# ETH.net
KiCad netlist of a schematic drawn in Altium Designer
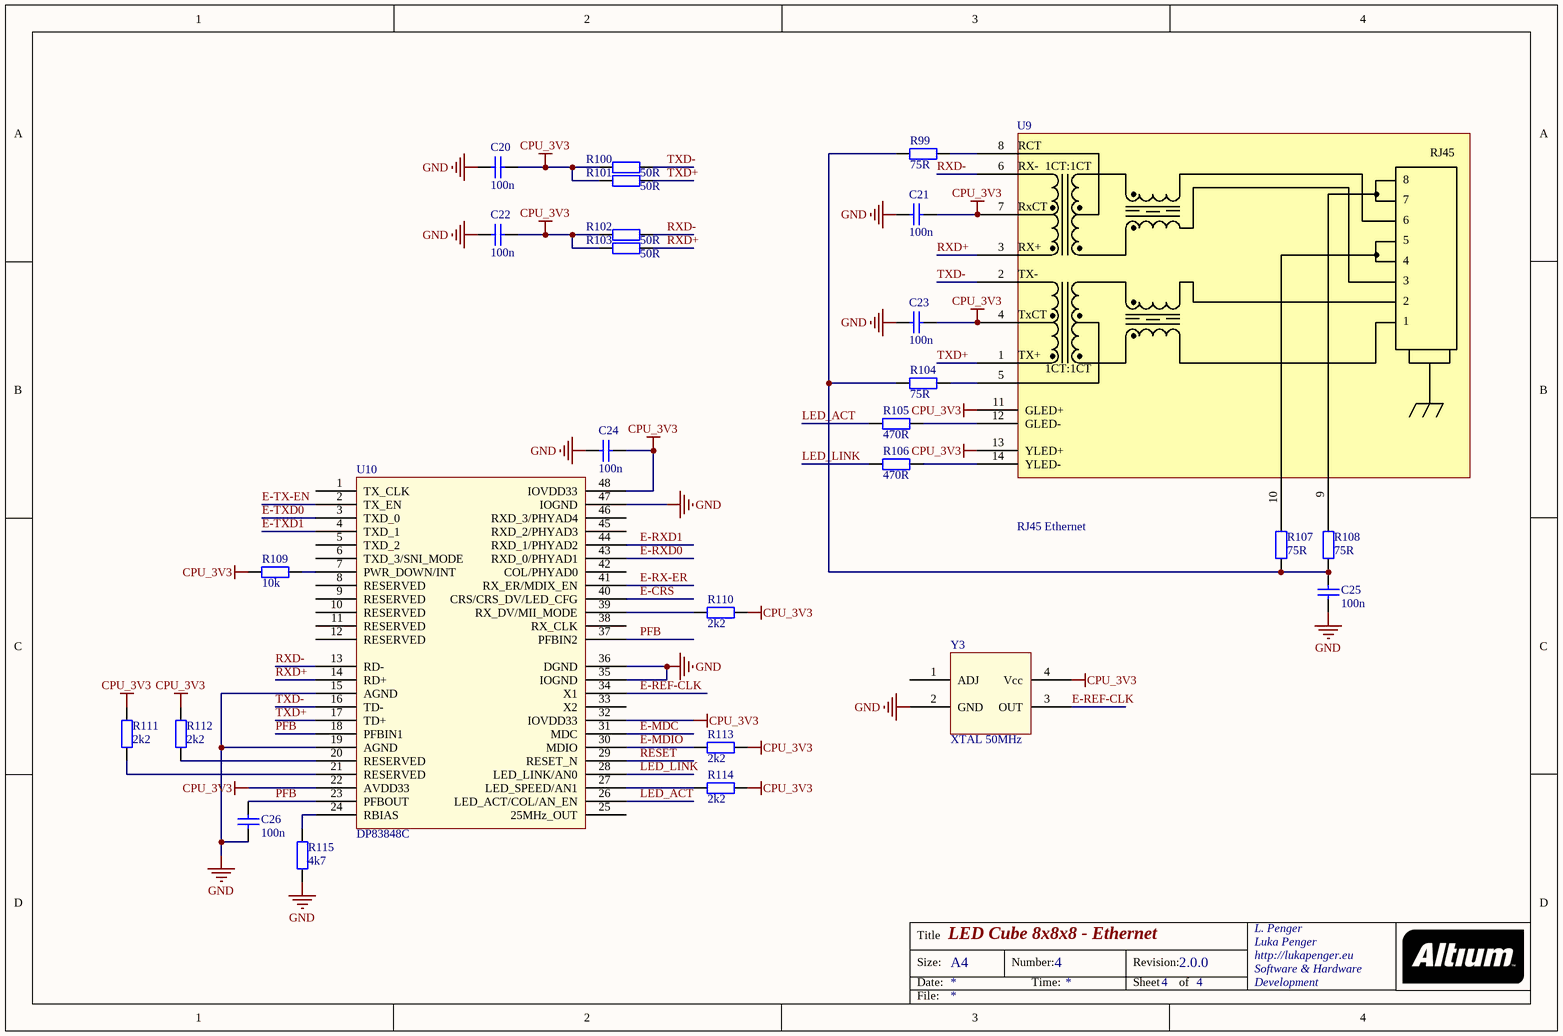
[diagram p0: ETH.SchDoc]

(export (version "E")
  (design (tool "Eeschema 10.0.6"))
  (components
    (comp (ref "C20")
      (value "100n")
      (footprint "1608[0603]")
      (description "Capacitor")
      (fields (field (name "PUBLISHER") "Altium Limited"))
      (libsource (lib "Miscellaneous Devices") (part "Cap"))
    )
    (comp (ref "C21")
      (value "100n")
      (footprint "1608[0603]")
      (description "Capacitor")
      (fields (field (name "PUBLISHER") "Altium Limited"))
      (libsource (lib "Miscellaneous Devices") (part "Cap"))
    )
    (comp (ref "C22")
      (value "100n")
      (footprint "1608[0603]")
      (description "Capacitor")
      (fields (field (name "PUBLISHER") "Altium Limited"))
      (libsource (lib "Miscellaneous Devices") (part "Cap"))
    )
    (comp (ref "C23")
      (value "100n")
      (footprint "1608[0603]")
      (description "Capacitor")
      (fields (field (name "PUBLISHER") "Altium Limited"))
      (libsource (lib "Miscellaneous Devices") (part "Cap"))
    )
    (comp (ref "C24")
      (value "100n")
      (footprint "1608[0603]")
      (description "Capacitor")
      (fields (field (name "PUBLISHER") "Altium Limited"))
      (libsource (lib "Miscellaneous Devices") (part "Cap"))
    )
    (comp (ref "C25")
      (value "100n")
      (footprint "1608[0603]")
      (description "Capacitor")
      (fields (field (name "PUBLISHER") "Altium Limited"))
      (libsource (lib "Miscellaneous Devices") (part "Cap"))
    )
    (comp (ref "C26")
      (value "100n")
      (footprint "6-0805_L")
      (description "Capacitor")
      (fields (field (name "PUBLISHER") "Altium Limited"))
      (libsource (lib "Miscellaneous Devices") (part "Cap"))
    )
    (comp (ref "R99")
      (value "75R")
      (footprint "1608[0603]")
      (description "Resistor")
      (fields (field (name "PUBLISHER") "Altium Limited"))
      (libsource (lib "Miscellaneous Devices") (part "Res2"))
    )
    (comp (ref "R100")
      (value "50R")
      (footprint "1608[0603]")
      (description "Resistor")
      (fields (field (name "PUBLISHER") "Altium Limited"))
      (libsource (lib "Miscellaneous Devices") (part "Res2"))
    )
    (comp (ref "R101")
      (value "50R")
      (footprint "1608[0603]")
      (description "Resistor")
      (fields (field (name "PUBLISHER") "Altium Limited"))
      (libsource (lib "Miscellaneous Devices") (part "Res2"))
    )
    (comp (ref "R102")
      (value "50R")
      (footprint "1608[0603]")
      (description "Resistor")
      (fields (field (name "PUBLISHER") "Altium Limited"))
      (libsource (lib "Miscellaneous Devices") (part "Res2"))
    )
    (comp (ref "R103")
      (value "50R")
      (footprint "1608[0603]")
      (description "Resistor")
      (fields (field (name "PUBLISHER") "Altium Limited"))
      (libsource (lib "Miscellaneous Devices") (part "Res2"))
    )
    (comp (ref "R104")
      (value "75R")
      (footprint "1608[0603]")
      (description "Resistor")
      (fields (field (name "PUBLISHER") "Altium Limited"))
      (libsource (lib "Miscellaneous Devices") (part "Res2"))
    )
    (comp (ref "R105")
      (value "470R")
      (footprint "1608[0603]")
      (description "Resistor")
      (fields (field (name "PUBLISHER") "Altium Limited"))
      (libsource (lib "Miscellaneous Devices") (part "Res2"))
    )
    (comp (ref "R106")
      (value "470R")
      (footprint "1608[0603]")
      (description "Resistor")
      (fields (field (name "PUBLISHER") "Altium Limited"))
      (libsource (lib "Miscellaneous Devices") (part "Res2"))
    )
    (comp (ref "R107")
      (value "75R")
      (footprint "1608[0603]")
      (description "Resistor")
      (fields (field (name "PUBLISHER") "Altium Limited"))
      (libsource (lib "") (part "Res2_1"))
    )
    (comp (ref "R108")
      (value "75R")
      (footprint "1608[0603]")
      (description "Resistor")
      (fields (field (name "PUBLISHER") "Altium Limited"))
      (libsource (lib "") (part "Res2_1"))
    )
    (comp (ref "R109")
      (value "10k")
      (footprint "1608[0603]")
      (description "Resistor")
      (fields (field (name "PUBLISHER") "Altium Limited"))
      (libsource (lib "Miscellaneous Devices") (part "Res2"))
    )
    (comp (ref "R110")
      (value "2k2")
      (footprint "1608[0603]")
      (description "Resistor")
      (fields (field (name "PUBLISHER") "Altium Limited"))
      (libsource (lib "Miscellaneous Devices") (part "Res2"))
    )
    (comp (ref "R111")
      (value "2k2")
      (footprint "1608[0603]")
      (description "Resistor")
      (fields (field (name "PUBLISHER") "Altium Limited"))
      (libsource (lib "") (part "Res2_2"))
    )
    (comp (ref "R112")
      (value "2k2")
      (footprint "1608[0603]")
      (description "Resistor")
      (fields (field (name "PUBLISHER") "Altium Limited"))
      (libsource (lib "") (part "Res2_1"))
    )
    (comp (ref "R113")
      (value "2k2")
      (footprint "1608[0603]")
      (description "Resistor")
      (fields (field (name "PUBLISHER") "Altium Limited"))
      (libsource (lib "Miscellaneous Devices") (part "Res2"))
    )
    (comp (ref "R114")
      (value "2k2")
      (footprint "1608[0603]")
      (description "Resistor")
      (fields (field (name "PUBLISHER") "Altium Limited"))
      (libsource (lib "Miscellaneous Devices") (part "Res2"))
    )
    (comp (ref "R115")
      (value "4k7")
      (footprint "1608[0603]")
      (description "Resistor")
      (fields (field (name "PUBLISHER") "Altium Limited"))
      (libsource (lib "") (part "Res2_2"))
    )
    (comp (ref "U9")
      (value "RJ45 Ethernet")
      (footprint "RJ45 Ethernet connector")
      (description "Ethernet Connector")
      (libsource (lib "LP_Lib") (part "RJ45 Ethernet"))
    )
    (comp (ref "U10")
      (value "DP83848C")
      (footprint "DP83848C")
      (description "Ethernet PHY")
      (libsource (lib "LP_Lib") (part "DP83848C"))
    )
    (comp (ref "Y3")
      (value "XTAL 50MHz")
      (footprint "XTAL ACT9200")
      (libsource (lib "LP_Lib") (part "XTAL ACT9200"))
    )
  )
  (nets
    (net (code "1") (name "/E-CRS") (class "Default")
      (node (ref "U10") (pin "40") (pinfunction "CRS/CRS_DV/LED_CFG_40") (pintype "passive"))
    )
    (net (code "2") (name "/E-MDC") (class "Default")
      (node (ref "U10") (pin "31") (pinfunction "MDC_31") (pintype "passive"))
    )
    (net (code "3") (name "/E-MDIO") (class "Default")
      (node (ref "R113") (pin "2") (pinfunction "2_2") (pintype "passive"))
      (node (ref "U10") (pin "30") (pinfunction "MDIO_30") (pintype "passive"))
    )
    (net (code "4") (name "/E-REF-CLK") (class "Default")
      (node (ref "U10") (pin "34") (pinfunction "X1_34") (pintype "passive"))
      (node (ref "Y3") (pin "3") (pinfunction "OUT_3") (pintype "passive"))
    )
    (net (code "5") (name "/E-RX-ER") (class "Default")
      (node (ref "U10") (pin "41") (pinfunction "RX_ER/MDIX_EN_41") (pintype "passive"))
    )
    (net (code "6") (name "/E-RXD0") (class "Default")
      (node (ref "U10") (pin "43") (pinfunction "RXD_0/PHYAD1_43") (pintype "passive"))
    )
    (net (code "7") (name "/E-RXD1") (class "Default")
      (node (ref "U10") (pin "44") (pinfunction "RXD_1/PHYAD2_44") (pintype "passive"))
    )
    (net (code "8") (name "/E-TX-EN") (class "Default")
      (node (ref "U10") (pin "2") (pinfunction "TX_EN_2") (pintype "passive"))
    )
    (net (code "9") (name "/E-TXD0") (class "Default")
      (node (ref "U10") (pin "3") (pinfunction "TXD_0_3") (pintype "passive"))
    )
    (net (code "10") (name "/E-TXD1") (class "Default")
      (node (ref "U10") (pin "4") (pinfunction "TXD_1_4") (pintype "passive"))
    )
    (net (code "11") (name "/LED_ACT") (class "Default")
      (node (ref "R105") (pin "2") (pinfunction "2_2") (pintype "passive"))
      (node (ref "U10") (pin "26") (pinfunction "LED_ACT/COL/AN_EN_26") (pintype "passive"))
    )
    (net (code "12") (name "/LED_LINK") (class "Default")
      (node (ref "R106") (pin "2") (pinfunction "2_2") (pintype "passive"))
      (node (ref "U10") (pin "28") (pinfunction "LED_LINK/AN0_28") (pintype "passive"))
    )
    (net (code "13") (name "/PFB") (class "Default")
      (node (ref "C26") (pin "1") (pinfunction "1_1") (pintype "passive"))
      (node (ref "U10") (pin "18") (pinfunction "PFBIN1_18") (pintype "passive"))
      (node (ref "U10") (pin "23") (pinfunction "PFBOUT_23") (pintype "passive"))
      (node (ref "U10") (pin "37") (pinfunction "PFBIN2_37") (pintype "passive"))
    )
    (net (code "14") (name "/RESET") (class "Default")
      (node (ref "U10") (pin "29") (pinfunction "RESET_N_29") (pintype "passive"))
    )
    (net (code "15") (name "/RXD+") (class "Default")
      (node (ref "R103") (pin "1") (pinfunction "1_1") (pintype "passive"))
      (node (ref "U10") (pin "14") (pinfunction "RD+_14") (pintype "passive"))
      (node (ref "U9") (pin "3") (pintype "passive"))
    )
    (net (code "16") (name "/RXD-") (class "Default")
      (node (ref "R102") (pin "1") (pinfunction "1_1") (pintype "passive"))
      (node (ref "U10") (pin "13") (pinfunction "RD-_13") (pintype "passive"))
      (node (ref "U9") (pin "6") (pintype "passive"))
    )
    (net (code "17") (name "/TXD+") (class "Default")
      (node (ref "R101") (pin "1") (pinfunction "1_1") (pintype "passive"))
      (node (ref "U10") (pin "17") (pinfunction "TD+_17") (pintype "passive"))
      (node (ref "U9") (pin "1") (pintype "passive"))
    )
    (net (code "18") (name "/TXD-") (class "Default")
      (node (ref "R100") (pin "1") (pinfunction "1_1") (pintype "passive"))
      (node (ref "U10") (pin "16") (pinfunction "TD-_16") (pintype "passive"))
      (node (ref "U9") (pin "2") (pintype "passive"))
    )
    (net (code "19") (name "CPU_3V3") (class "Default")
      (node (ref "C20") (pin "2") (pinfunction "2_2") (pintype "passive"))
      (node (ref "C21") (pin "2") (pinfunction "2_2") (pintype "passive"))
      (node (ref "C22") (pin "2") (pinfunction "2_2") (pintype "passive"))
      (node (ref "C23") (pin "2") (pinfunction "2_2") (pintype "passive"))
      (node (ref "C24") (pin "2") (pinfunction "2_2") (pintype "passive"))
      (node (ref "R100") (pin "2") (pinfunction "2_2") (pintype "passive"))
      (node (ref "R101") (pin "2") (pinfunction "2_2") (pintype "passive"))
      (node (ref "R102") (pin "2") (pinfunction "2_2") (pintype "passive"))
      (node (ref "R103") (pin "2") (pinfunction "2_2") (pintype "passive"))
      (node (ref "R109") (pin "2") (pinfunction "2_2") (pintype "passive"))
      (node (ref "R110") (pin "1") (pinfunction "1_1") (pintype "passive"))
      (node (ref "R111") (pin "1") (pinfunction "1_1") (pintype "passive"))
      (node (ref "R112") (pin "2") (pinfunction "2_2") (pintype "passive"))
      (node (ref "R113") (pin "1") (pinfunction "1_1") (pintype "passive"))
      (node (ref "R114") (pin "1") (pinfunction "1_1") (pintype "passive"))
      (node (ref "U10") (pin "22") (pinfunction "AVDD33_22") (pintype "passive"))
      (node (ref "U10") (pin "32") (pinfunction "IOVDD33_32") (pintype "passive"))
      (node (ref "U10") (pin "48") (pinfunction "IOVDD33_48") (pintype "passive"))
      (node (ref "U9") (pin "11") (pinfunction "GLED+_11") (pintype "passive"))
      (node (ref "U9") (pin "13") (pinfunction "YLED+_13") (pintype "passive"))
      (node (ref "U9") (pin "4") (pintype "passive"))
      (node (ref "U9") (pin "7") (pintype "passive"))
      (node (ref "Y3") (pin "4") (pinfunction "Vcc_4") (pintype "passive"))
    )
    (net (code "20") (name "GND") (class "Default")
      (node (ref "C20") (pin "1") (pinfunction "1_1") (pintype "passive"))
      (node (ref "C21") (pin "1") (pinfunction "1_1") (pintype "passive"))
      (node (ref "C22") (pin "1") (pinfunction "1_1") (pintype "passive"))
      (node (ref "C23") (pin "1") (pinfunction "1_1") (pintype "passive"))
      (node (ref "C24") (pin "1") (pinfunction "1_1") (pintype "passive"))
      (node (ref "C25") (pin "2") (pinfunction "2_2") (pintype "passive"))
      (node (ref "C26") (pin "2") (pinfunction "2_2") (pintype "passive"))
      (node (ref "R115") (pin "2") (pinfunction "2_2") (pintype "passive"))
      (node (ref "U10") (pin "15") (pinfunction "AGND_15") (pintype "passive"))
      (node (ref "U10") (pin "19") (pinfunction "AGND_19") (pintype "passive"))
      (node (ref "U10") (pin "35") (pinfunction "IOGND_35") (pintype "passive"))
      (node (ref "U10") (pin "36") (pinfunction "DGND_36") (pintype "passive"))
      (node (ref "U10") (pin "47") (pinfunction "IOGND_47") (pintype "passive"))
      (node (ref "Y3") (pin "2") (pinfunction "GND_2") (pintype "passive"))
    )
    (net (code "21") (name "Net-(C25-Pad1)") (class "Default")
      (node (ref "C25") (pin "1") (pinfunction "1_1") (pintype "passive"))
      (node (ref "R104") (pin "2") (pinfunction "2_2") (pintype "passive"))
      (node (ref "R107") (pin "1") (pinfunction "1_1") (pintype "passive"))
      (node (ref "R108") (pin "1") (pinfunction "1_1") (pintype "passive"))
      (node (ref "R99") (pin "2") (pinfunction "2_2") (pintype "passive"))
    )
    (net (code "22") (name "Net-(R99-Pad1)") (class "Default")
      (node (ref "R99") (pin "1") (pinfunction "1_1") (pintype "passive"))
      (node (ref "U9") (pin "8") (pintype "passive"))
    )
    (net (code "23") (name "Net-(R104-Pad1)") (class "Default")
      (node (ref "R104") (pin "1") (pinfunction "1_1") (pintype "passive"))
      (node (ref "U9") (pin "5") (pintype "passive"))
    )
    (net (code "24") (name "Net-(R107-Pad2)") (class "Default")
      (node (ref "R107") (pin "2") (pinfunction "2_2") (pintype "passive"))
      (node (ref "U9") (pin "10") (pintype "passive"))
    )
    (net (code "25") (name "Net-(R108-Pad2)") (class "Default")
      (node (ref "R108") (pin "2") (pinfunction "2_2") (pintype "passive"))
      (node (ref "U9") (pin "9") (pintype "passive"))
    )
    (net (code "26") (name "Net-(R111-Pad2)") (class "Default")
      (node (ref "R111") (pin "2") (pinfunction "2_2") (pintype "passive"))
      (node (ref "U10") (pin "21") (pinfunction "RESERVED_21") (pintype "passive"))
    )
    (net (code "27") (name "Net-(R112-Pad1)") (class "Default")
      (node (ref "R112") (pin "1") (pinfunction "1_1") (pintype "passive"))
      (node (ref "U10") (pin "20") (pinfunction "RESERVED_20") (pintype "passive"))
    )
    (net (code "28") (name "Net-(U9-GLED-)") (class "Default")
      (node (ref "R105") (pin "1") (pinfunction "1_1") (pintype "passive"))
      (node (ref "U9") (pin "12") (pinfunction "GLED-_12") (pintype "passive"))
    )
    (net (code "29") (name "Net-(U9-YLED-)") (class "Default")
      (node (ref "R106") (pin "1") (pinfunction "1_1") (pintype "passive"))
      (node (ref "U9") (pin "14") (pinfunction "YLED-_14") (pintype "passive"))
    )
    (net (code "30") (name "Net-(U10-LED_SPEED{slash}AN1)") (class "Default")
      (node (ref "R114") (pin "2") (pinfunction "2_2") (pintype "passive"))
      (node (ref "U10") (pin "27") (pinfunction "LED_SPEED/AN1_27") (pintype "passive"))
    )
    (net (code "31") (name "Net-(U10-PWR_DOWN{slash}INT)") (class "Default")
      (node (ref "R109") (pin "1") (pinfunction "1_1") (pintype "passive"))
      (node (ref "U10") (pin "7") (pinfunction "PWR_DOWN/INT_7") (pintype "passive"))
    )
    (net (code "32") (name "Net-(U10-RBIAS)") (class "Default")
      (node (ref "R115") (pin "1") (pinfunction "1_1") (pintype "passive"))
      (node (ref "U10") (pin "24") (pinfunction "RBIAS_24") (pintype "passive"))
    )
    (net (code "33") (name "Net-(U10-RX_DV{slash}MII_MODE)") (class "Default")
      (node (ref "R110") (pin "2") (pinfunction "2_2") (pintype "passive"))
      (node (ref "U10") (pin "39") (pinfunction "RX_DV/MII_MODE_39") (pintype "passive"))
    )
    (net (code "34") (name "unconnected-(U10-25MHz_OUT-Pad25)") (class "Default")
      (node (ref "U10") (pin "25") (pinfunction "25MHz_OUT_25") (pintype "passive"))
    )
    (net (code "35") (name "unconnected-(U10-COL{slash}PHYAD0-Pad42)") (class "Default")
      (node (ref "U10") (pin "42") (pinfunction "COL/PHYAD0_42") (pintype "passive"))
    )
    (net (code "36") (name "unconnected-(U10-RESERVED-Pad8)") (class "Default")
      (node (ref "U10") (pin "8") (pinfunction "RESERVED_8") (pintype "passive"))
    )
    (net (code "37") (name "unconnected-(U10-RESERVED-Pad9)") (class "Default")
      (node (ref "U10") (pin "9") (pinfunction "RESERVED_9") (pintype "passive"))
    )
    (net (code "38") (name "unconnected-(U10-RESERVED-Pad10)") (class "Default")
      (node (ref "U10") (pin "10") (pinfunction "RESERVED_10") (pintype "passive"))
    )
    (net (code "39") (name "unconnected-(U10-RESERVED-Pad11)") (class "Default")
      (node (ref "U10") (pin "11") (pinfunction "RESERVED_11") (pintype "passive"))
    )
    (net (code "40") (name "unconnected-(U10-RESERVED-Pad12)") (class "Default")
      (node (ref "U10") (pin "12") (pinfunction "RESERVED_12") (pintype "passive"))
    )
    (net (code "41") (name "unconnected-(U10-RXD_2{slash}PHYAD3-Pad45)") (class "Default")
      (node (ref "U10") (pin "45") (pinfunction "RXD_2/PHYAD3_45") (pintype "passive"))
    )
    (net (code "42") (name "unconnected-(U10-RXD_3{slash}PHYAD4-Pad46)") (class "Default")
      (node (ref "U10") (pin "46") (pinfunction "RXD_3/PHYAD4_46") (pintype "passive"))
    )
    (net (code "43") (name "unconnected-(U10-RX_CLK-Pad38)") (class "Default")
      (node (ref "U10") (pin "38") (pinfunction "RX_CLK_38") (pintype "passive"))
    )
    (net (code "44") (name "unconnected-(U10-TXD_2-Pad5)") (class "Default")
      (node (ref "U10") (pin "5") (pinfunction "TXD_2_5") (pintype "passive"))
    )
    (net (code "45") (name "unconnected-(U10-TXD_3{slash}SNI_MODE-Pad6)") (class "Default")
      (node (ref "U10") (pin "6") (pinfunction "TXD_3/SNI_MODE_6") (pintype "passive"))
    )
    (net (code "46") (name "unconnected-(U10-TX_CLK-Pad1)") (class "Default")
      (node (ref "U10") (pin "1") (pinfunction "TX_CLK_1") (pintype "passive"))
    )
    (net (code "47") (name "unconnected-(U10-X2-Pad33)") (class "Default")
      (node (ref "U10") (pin "33") (pinfunction "X2_33") (pintype "passive"))
    )
    (net (code "48") (name "unconnected-(Y3-ADJ-Pad1)") (class "Default")
      (node (ref "Y3") (pin "1") (pinfunction "ADJ_1") (pintype "passive"))
    )
  )
)
